# CYAN_EVSE_Logic_board_v1_2.net
KiCad netlist of a schematic drawn in Altium Designer
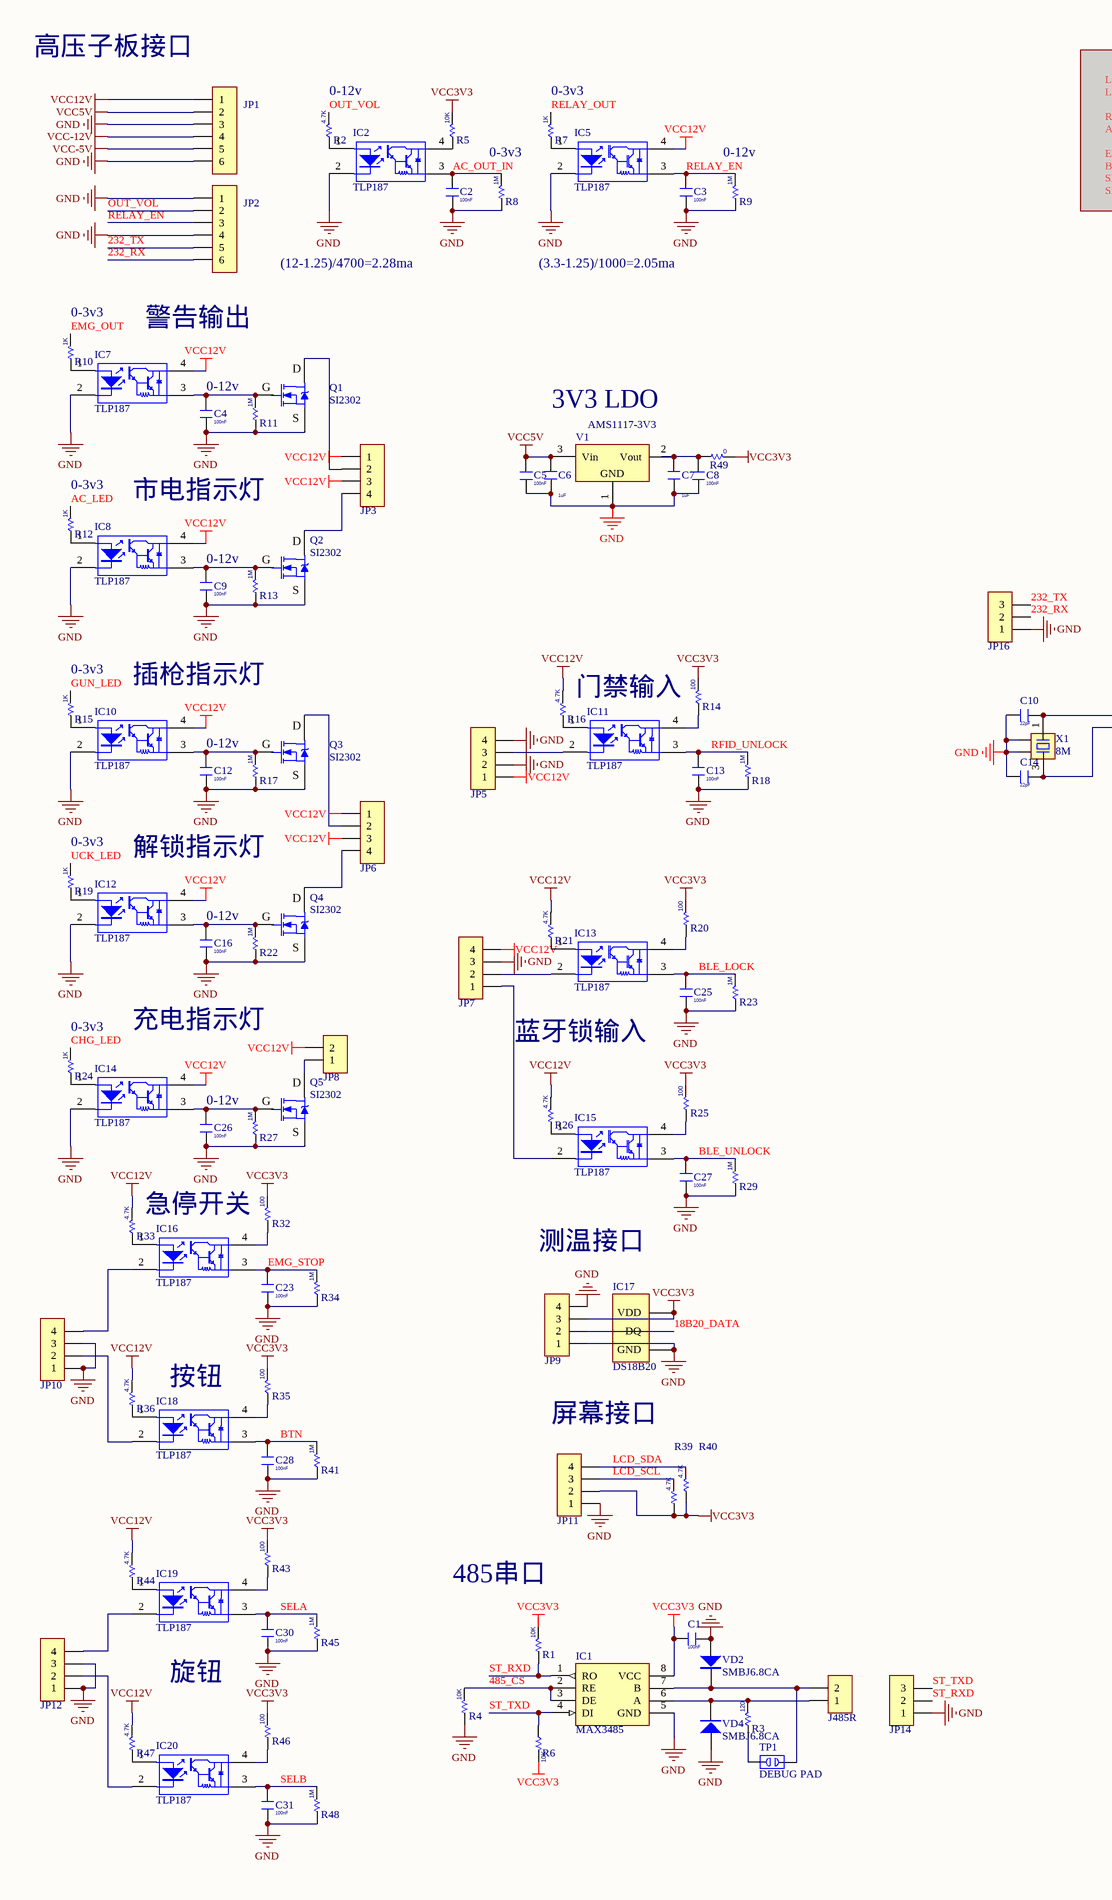
[diagram p0: CYAN_EVSE_Logic_board_v1.2.SchDoc, left]
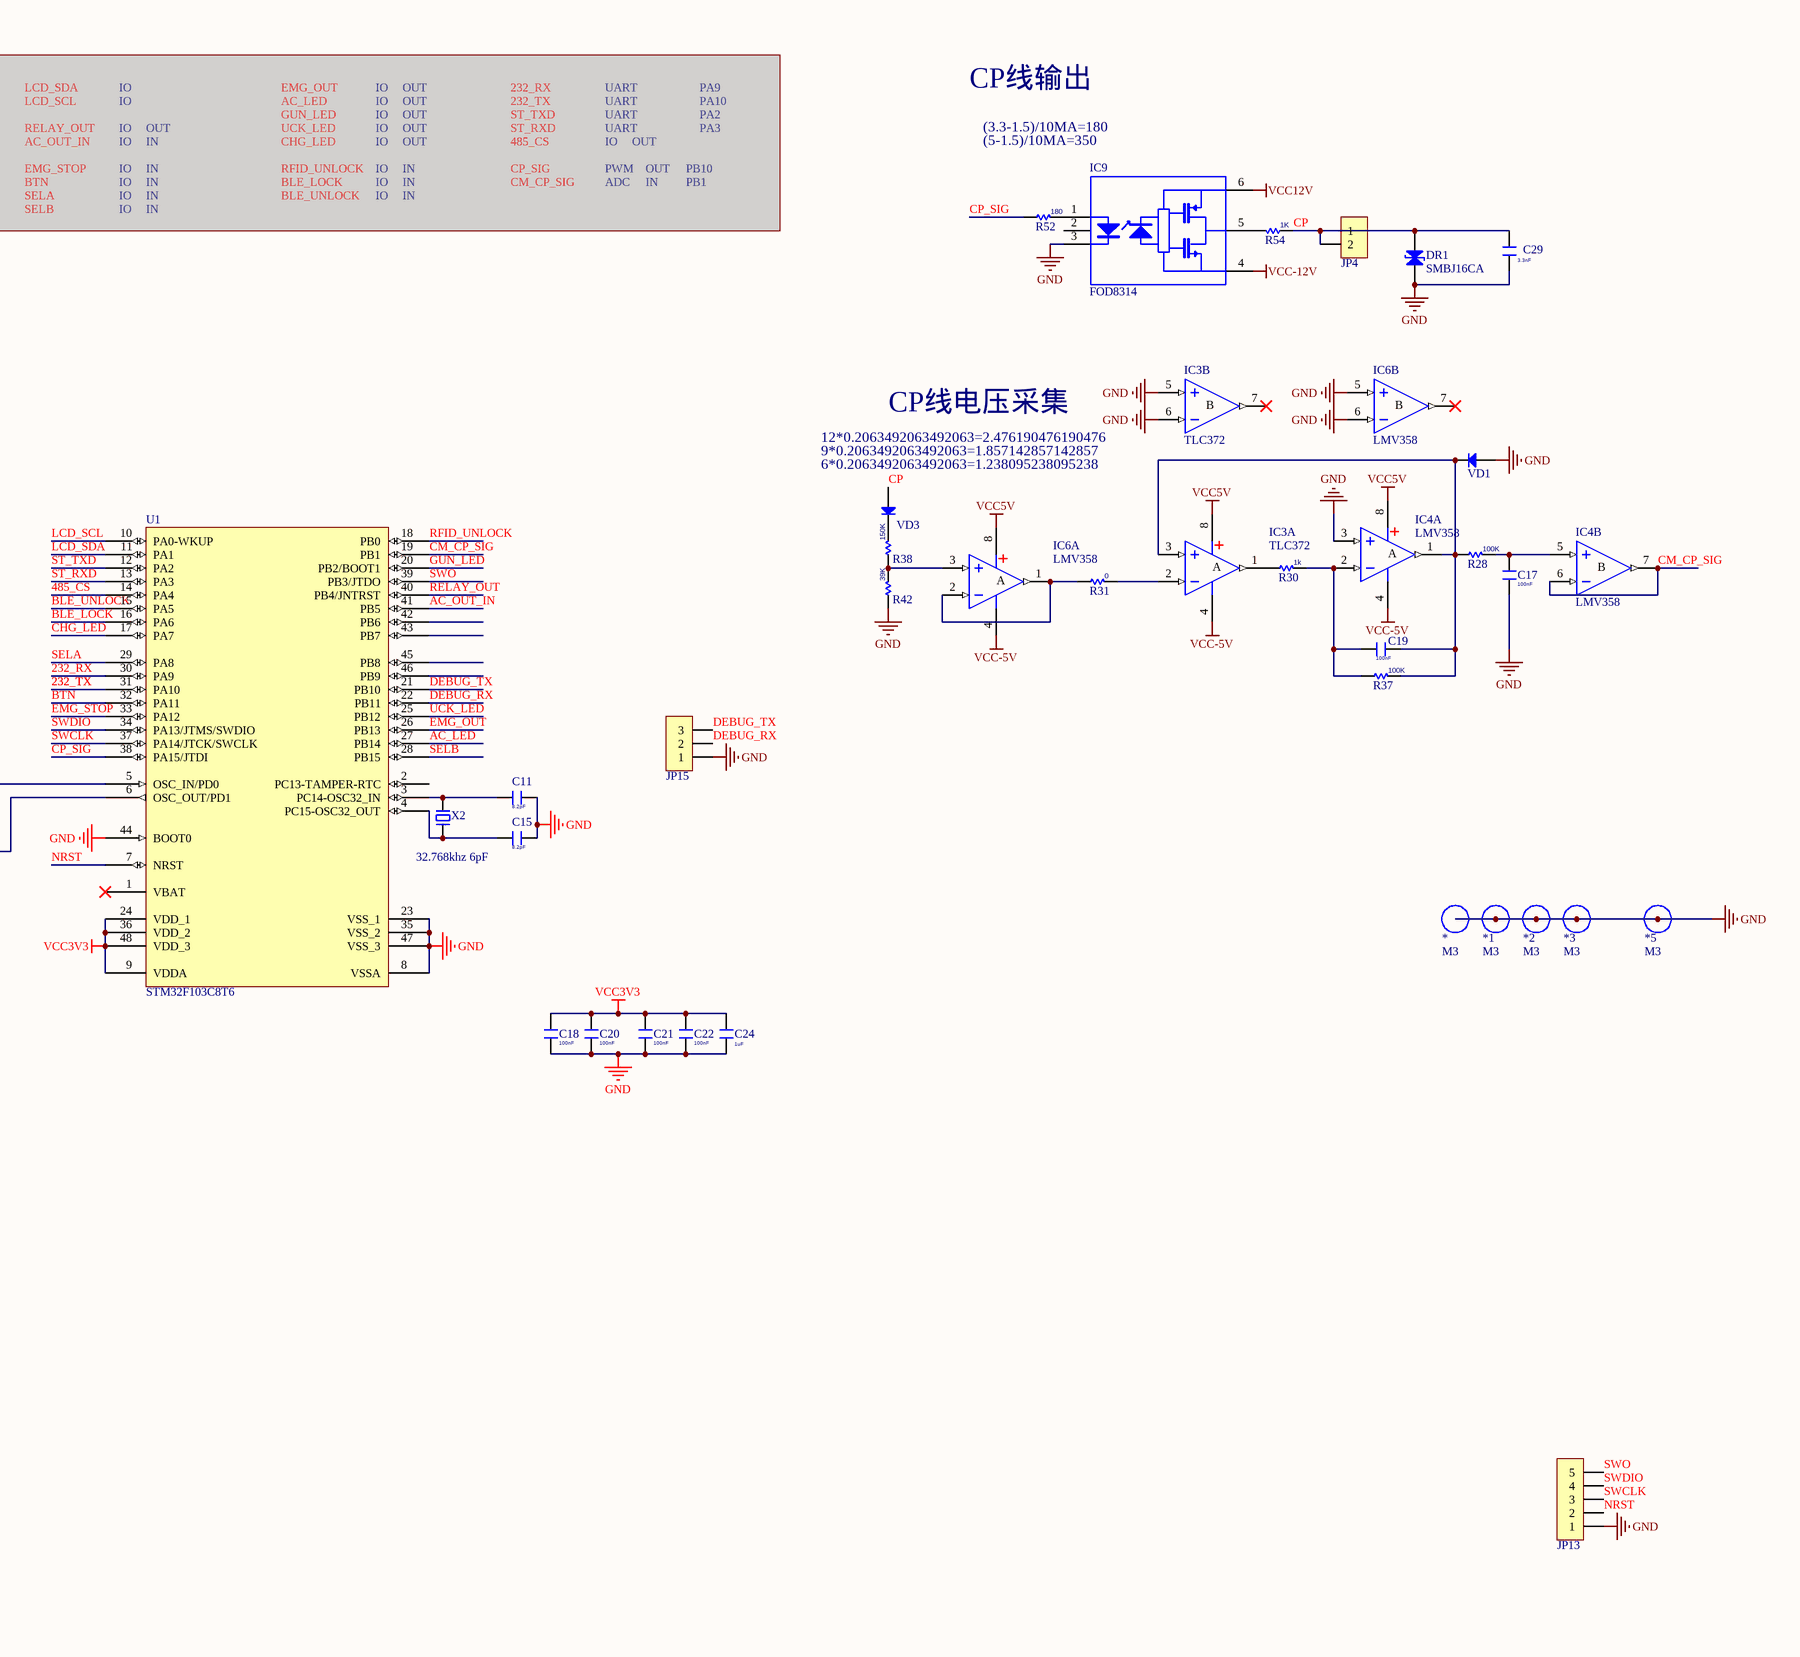
[diagram p1: CYAN_EVSE_Logic_board_v1.2.SchDoc, right]

(export (version "E")
  (design (tool "Eeschema 10.0.6"))
  (components
    (comp (ref "*")
      (value "M3")
      (footprint "M3 125X300")
      (description "铜柱孔")
      (libsource (lib "未分类器件") (part "M3"))
    )
    (comp (ref "*1")
      (value "M3")
      (footprint "M3 125X300")
      (description "铜柱孔")
      (libsource (lib "未分类器件") (part "M3"))
    )
    (comp (ref "*2")
      (value "M3")
      (footprint "M3 125X300")
      (description "铜柱孔")
      (libsource (lib "未分类器件") (part "M3"))
    )
    (comp (ref "*3")
      (value "M3")
      (footprint "M3 125X300")
      (description "铜柱孔")
      (libsource (lib "未分类器件") (part "M3"))
    )
    (comp (ref "*5")
      (value "M3")
      (footprint "M3 125X300")
      (description "铜柱孔")
      (libsource (lib "未分类器件") (part "M3"))
    )
    (comp (ref "C1")
      (value "100nF")
      (footprint "C 0805")
      (description "无极性贴片电容")
      (fields (field (name "VOLTAGE") "20V") (field (name "Comment") "C"))
      (libsource (lib "电阻-电容-电感") (part "C"))
    )
    (comp (ref "C2")
      (value "100nF")
      (footprint "C 0805")
      (description "无极性贴片电容")
      (fields (field (name "VOLTAGE") "20V") (field (name "Comment") "C"))
      (libsource (lib "电阻-电容-电感") (part "C"))
    )
    (comp (ref "C3")
      (value "100nF")
      (footprint "C 0805")
      (description "无极性贴片电容")
      (fields (field (name "VOLTAGE") "20V") (field (name "Comment") "C"))
      (libsource (lib "电阻-电容-电感") (part "C"))
    )
    (comp (ref "C4")
      (value "100nF")
      (footprint "C 0805")
      (description "无极性贴片电容")
      (fields (field (name "VOLTAGE") "20V") (field (name "Comment") "C"))
      (libsource (lib "电阻-电容-电感") (part "C"))
    )
    (comp (ref "C5")
      (value "100nF")
      (footprint "C 0805")
      (description "无极性贴片电容")
      (fields (field (name "VOLTAGE") "20V") (field (name "Comment") "C"))
      (libsource (lib "电阻-电容-电感") (part "C"))
    )
    (comp (ref "C6")
      (value "1uF")
      (footprint "C 0805")
      (description "无极性贴片电容")
      (fields (field (name "Comment") "C"))
      (libsource (lib "电阻-电容-电感") (part "C"))
    )
    (comp (ref "C7")
      (value "1uF")
      (footprint "C 0805")
      (description "无极性贴片电容")
      (fields (field (name "Comment") "C"))
      (libsource (lib "电阻-电容-电感") (part "C"))
    )
    (comp (ref "C8")
      (value "100nF")
      (footprint "C 0805")
      (description "无极性贴片电容")
      (fields (field (name "VOLTAGE") "20V") (field (name "Comment") "C"))
      (libsource (lib "电阻-电容-电感") (part "C"))
    )
    (comp (ref "C9")
      (value "100nF")
      (footprint "C 0805")
      (description "无极性贴片电容")
      (fields (field (name "VOLTAGE") "20V") (field (name "Comment") "C"))
      (libsource (lib "电阻-电容-电感") (part "C"))
    )
    (comp (ref "C10")
      (value "22pF")
      (footprint "C 0805")
      (description "无极性贴片电容")
      (fields (field (name "VOLTAGE") "20V") (field (name "Comment") "C"))
      (libsource (lib "电阻-电容-电感") (part "C"))
    )
    (comp (ref "C11")
      (value "8.2pF")
      (footprint "C 0805")
      (description "无极性贴片电容")
      (fields (field (name "VOLTAGE") "20V") (field (name "Comment") "C"))
      (libsource (lib "电阻-电容-电感") (part "C"))
    )
    (comp (ref "C12")
      (value "100nF")
      (footprint "C 0805")
      (description "无极性贴片电容")
      (fields (field (name "VOLTAGE") "20V") (field (name "Comment") "C"))
      (libsource (lib "电阻-电容-电感") (part "C"))
    )
    (comp (ref "C13")
      (value "100nF")
      (footprint "C 0805")
      (description "无极性贴片电容")
      (fields (field (name "VOLTAGE") "20V") (field (name "Comment") "C"))
      (libsource (lib "电阻-电容-电感") (part "C"))
    )
    (comp (ref "C14")
      (value "22pF")
      (footprint "C 0805")
      (description "无极性贴片电容")
      (fields (field (name "VOLTAGE") "20V") (field (name "Comment") "C"))
      (libsource (lib "电阻-电容-电感") (part "C"))
    )
    (comp (ref "C15")
      (value "8.2pF")
      (footprint "C 0805")
      (description "无极性贴片电容")
      (fields (field (name "VOLTAGE") "20V") (field (name "Comment") "C"))
      (libsource (lib "电阻-电容-电感") (part "C"))
    )
    (comp (ref "C16")
      (value "100nF")
      (footprint "C 0805")
      (description "无极性贴片电容")
      (fields (field (name "VOLTAGE") "20V") (field (name "Comment") "C"))
      (libsource (lib "电阻-电容-电感") (part "C"))
    )
    (comp (ref "C17")
      (value "100nF")
      (footprint "C 0805")
      (description "无极性贴片电容")
      (fields (field (name "VOLTAGE") "20V") (field (name "Comment") "C"))
      (libsource (lib "电阻-电容-电感") (part "C"))
    )
    (comp (ref "C18")
      (value "100nF")
      (footprint "C 0805")
      (description "无极性贴片电容")
      (fields (field (name "VOLTAGE") "20V") (field (name "Comment") "C"))
      (libsource (lib "电阻-电容-电感") (part "C"))
    )
    (comp (ref "C19")
      (value "100nF")
      (footprint "C 0805")
      (description "无极性贴片电容")
      (fields (field (name "VOLTAGE") "20V") (field (name "Comment") "C"))
      (libsource (lib "电阻-电容-电感") (part "C"))
    )
    (comp (ref "C20")
      (value "100nF")
      (footprint "C 0805")
      (description "无极性贴片电容")
      (fields (field (name "VOLTAGE") "20V") (field (name "Comment") "C"))
      (libsource (lib "电阻-电容-电感") (part "C"))
    )
    (comp (ref "C21")
      (value "100nF")
      (footprint "C 0805")
      (description "无极性贴片电容")
      (fields (field (name "VOLTAGE") "20V") (field (name "Comment") "C"))
      (libsource (lib "电阻-电容-电感") (part "C"))
    )
    (comp (ref "C22")
      (value "100nF")
      (footprint "C 0805")
      (description "无极性贴片电容")
      (fields (field (name "VOLTAGE") "20V") (field (name "Comment") "C"))
      (libsource (lib "电阻-电容-电感") (part "C"))
    )
    (comp (ref "C23")
      (value "100nF")
      (footprint "C 0805")
      (description "无极性贴片电容")
      (fields (field (name "VOLTAGE") "20V") (field (name "Comment") "C"))
      (libsource (lib "电阻-电容-电感") (part "C"))
    )
    (comp (ref "C24")
      (value "1uF")
      (footprint "C 0805")
      (description "无极性贴片电容")
      (fields (field (name "Comment") "C"))
      (libsource (lib "电阻-电容-电感") (part "C"))
    )
    (comp (ref "C25")
      (value "100nF")
      (footprint "C 0805")
      (description "无极性贴片电容")
      (fields (field (name "VOLTAGE") "20V") (field (name "Comment") "C"))
      (libsource (lib "电阻-电容-电感") (part "C"))
    )
    (comp (ref "C26")
      (value "100nF")
      (footprint "C 0805")
      (description "无极性贴片电容")
      (fields (field (name "VOLTAGE") "20V") (field (name "Comment") "C"))
      (libsource (lib "电阻-电容-电感") (part "C"))
    )
    (comp (ref "C27")
      (value "100nF")
      (footprint "C 0805")
      (description "无极性贴片电容")
      (fields (field (name "VOLTAGE") "20V") (field (name "Comment") "C"))
      (libsource (lib "电阻-电容-电感") (part "C"))
    )
    (comp (ref "C28")
      (value "100nF")
      (footprint "C 0805")
      (description "无极性贴片电容")
      (fields (field (name "VOLTAGE") "20V") (field (name "Comment") "C"))
      (libsource (lib "电阻-电容-电感") (part "C"))
    )
    (comp (ref "C29")
      (value "3.3nF")
      (footprint "C 1206")
      (description "无极性贴片电容")
      (fields (field (name "VOLTAGE") "50V") (field (name "Comment") "C"))
      (libsource (lib "电阻-电容-电感") (part "C"))
    )
    (comp (ref "C30")
      (value "100nF")
      (footprint "C 0805")
      (description "无极性贴片电容")
      (fields (field (name "VOLTAGE") "20V") (field (name "Comment") "C"))
      (libsource (lib "电阻-电容-电感") (part "C"))
    )
    (comp (ref "C31")
      (value "100nF")
      (footprint "C 0805")
      (description "无极性贴片电容")
      (fields (field (name "VOLTAGE") "20V") (field (name "Comment") "C"))
      (libsource (lib "电阻-电容-电感") (part "C"))
    )
    (comp (ref "DR1")
      (value "SMBJ16CA")
      (footprint "SMB")
      (description "瞬态电压抑制二极管")
      (libsource (lib "二极管-整流桥") (part "DR"))
    )
    (comp (ref "IC1")
      (value "MAX3485")
      (footprint "SOP8_N")
      (description "RS485总线收发芯片")
      (libsource (lib "IC芯片") (part "MAX487"))
    )
    (comp (ref "IC2")
      (value "TLP187")
      (footprint "SOP6_4.6MM_W1.27_4PIN_N")
      (description "达林顿输出光耦")
      (libsource (lib "传感元件") (part "TLP187"))
    )
    (comp (ref "IC3")
      (value "TLC372")
      (footprint "SOP8_N")
      (description "双路电压比较,MOS下臂输出")
      (libsource (lib "IC芯片") (part "TLC372"))
    )
    (comp (ref "IC4")
      (value "LMV358")
      (footprint "SOP8_N")
      (description "双路运放")
      (libsource (lib "IC芯片") (part "LM358"))
    )
    (comp (ref "IC5")
      (value "TLP187")
      (footprint "SOP6_4.6MM_W1.27_4PIN_N")
      (description "达林顿输出光耦")
      (libsource (lib "传感元件") (part "TLP187"))
    )
    (comp (ref "IC6")
      (value "LMV358")
      (footprint "SOP8_N")
      (description "双路运放")
      (libsource (lib "IC芯片") (part "LM358"))
    )
    (comp (ref "IC7")
      (value "TLP187")
      (footprint "SOP6_4.6MM_W1.27_4PIN_N")
      (description "达林顿输出光耦")
      (libsource (lib "传感元件") (part "TLP187"))
    )
    (comp (ref "IC8")
      (value "TLP187")
      (footprint "SOP6_4.6MM_W1.27_4PIN_N")
      (description "达林顿输出光耦")
      (libsource (lib "传感元件") (part "TLP187"))
    )
    (comp (ref "IC9")
      (value "FOD8314")
      (footprint "SOP6_7MM_WIDE_LEAD_N")
      (description "MOSFET/IGBT 驱动光耦，15-30v 1a")
      (libsource (lib "传感元件") (part "FOD8314"))
    )
    (comp (ref "IC10")
      (value "TLP187")
      (footprint "SOP6_4.6MM_W1.27_4PIN_N")
      (description "达林顿输出光耦")
      (libsource (lib "传感元件") (part "TLP187"))
    )
    (comp (ref "IC11")
      (value "TLP187")
      (footprint "SOP6_4.6MM_W1.27_4PIN_N")
      (description "达林顿输出光耦")
      (libsource (lib "传感元件") (part "TLP187"))
    )
    (comp (ref "IC12")
      (value "TLP187")
      (footprint "SOP6_4.6MM_W1.27_4PIN_N")
      (description "达林顿输出光耦")
      (libsource (lib "传感元件") (part "TLP187"))
    )
    (comp (ref "IC13")
      (value "TLP187")
      (footprint "SOP6_4.6MM_W1.27_4PIN_N")
      (description "达林顿输出光耦")
      (libsource (lib "传感元件") (part "TLP187"))
    )
    (comp (ref "IC14")
      (value "TLP187")
      (footprint "SOP6_4.6MM_W1.27_4PIN_N")
      (description "达林顿输出光耦")
      (libsource (lib "传感元件") (part "TLP187"))
    )
    (comp (ref "IC15")
      (value "TLP187")
      (footprint "SOP6_4.6MM_W1.27_4PIN_N")
      (description "达林顿输出光耦")
      (libsource (lib "传感元件") (part "TLP187"))
    )
    (comp (ref "IC16")
      (value "TLP187")
      (footprint "SOP6_4.6MM_W1.27_4PIN_N")
      (description "达林顿输出光耦")
      (libsource (lib "传感元件") (part "TLP187"))
    )
    (comp (ref "IC17")
      (value "DS18B20")
      (footprint "TO92A")
      (description "数字温度计")
      (libsource (lib "IC芯片") (part "DS18B20"))
    )
    (comp (ref "IC18")
      (value "TLP187")
      (footprint "SOP6_4.6MM_W1.27_4PIN_N")
      (description "达林顿输出光耦")
      (libsource (lib "传感元件") (part "TLP187"))
    )
    (comp (ref "IC19")
      (value "TLP187")
      (footprint "SOP6_4.6MM_W1.27_4PIN_N")
      (description "达林顿输出光耦")
      (libsource (lib "传感元件") (part "TLP187"))
    )
    (comp (ref "IC20")
      (value "TLP187")
      (footprint "SOP6_4.6MM_W1.27_4PIN_N")
      (description "达林顿输出光耦")
      (libsource (lib "传感元件") (part "TLP187"))
    )
    (comp (ref "J485R")
      (value "HDR-1X2")
      (footprint "MC 1,5/ 2-G-3,81")
      (description "2P接插件")
      (libsource (lib "接插件") (part "Header 2"))
    )
    (comp (ref "JP1")
      (value "HDR-1X6")
      (footprint "XH2.54-6P")
      (description "6P接插件")
      (libsource (lib "接插件") (part "Header 6"))
    )
    (comp (ref "JP2")
      (value "HDR-1X6")
      (footprint "XH2.54-6P")
      (description "6P接插件")
      (libsource (lib "接插件") (part "Header 6"))
    )
    (comp (ref "JP3")
      (value "HDR-1X4")
      (footprint "MC 1,5/ 4-G-3,81")
      (description "4P接插件")
      (libsource (lib "") (part "Header 4_1"))
    )
    (comp (ref "JP4")
      (value "HDR-1X2")
      (footprint "MC 1,5/ 2-G-3,81")
      (description "2P接插件")
      (libsource (lib "") (part "Header 2_1"))
    )
    (comp (ref "JP5")
      (value "HDR-1X4")
      (footprint "MC 1,5/ 4-G-3,81")
      (description "4P接插件")
      (libsource (lib "接插件") (part "Header 4"))
    )
    (comp (ref "JP6")
      (value "HDR-1X4")
      (footprint "MC 1,5/ 4-G-3,81")
      (description "4P接插件")
      (libsource (lib "") (part "Header 4_1"))
    )
    (comp (ref "JP7")
      (value "HDR-1X4")
      (footprint "MC 1,5/ 4-G-3,81")
      (description "4P接插件")
      (libsource (lib "接插件") (part "Header 4"))
    )
    (comp (ref "JP8")
      (value "HDR-1X2")
      (footprint "MC 1,5/ 2-G-3,81")
      (description "2P接插件")
      (libsource (lib "接插件") (part "Header 2"))
    )
    (comp (ref "JP9")
      (value "HDR-1X4")
      (footprint "MC 1,5/ 4-G-3,81")
      (description "4P接插件")
      (libsource (lib "接插件") (part "Header 4"))
    )
    (comp (ref "JP10")
      (value "HDR-1X4")
      (footprint "MC 1,5/ 4-G-3,81")
      (description "4P接插件")
      (libsource (lib "接插件") (part "Header 4"))
    )
    (comp (ref "JP11")
      (value "HDR-1X4")
      (footprint "XH2.54-4P")
      (description "4P接插件")
      (libsource (lib "接插件") (part "Header 4"))
    )
    (comp (ref "JP12")
      (value "HDR-1X4")
      (footprint "MC 1,5/ 4-G-3,81")
      (description "4P接插件")
      (libsource (lib "接插件") (part "Header 4"))
    )
    (comp (ref "JP13")
      (value "HDR-1X5")
      (footprint "HDR-1X5")
      (description "5P接插件")
      (libsource (lib "接插件") (part "Header 5"))
    )
    (comp (ref "JP14")
      (value "HDR-1X3")
      (footprint "HDR-1X3")
      (description "3P接插件")
      (libsource (lib "接插件") (part "Header 3"))
    )
    (comp (ref "JP15")
      (value "HDR-1X3")
      (footprint "HDR-1X3")
      (description "3P接插件")
      (libsource (lib "接插件") (part "Header 3"))
    )
    (comp (ref "JP16")
      (value "HDR-1X3")
      (footprint "HDR-1X3")
      (description "3P接插件")
      (libsource (lib "接插件") (part "Header 3"))
    )
    (comp (ref "Q1")
      (value "SI2302")
      (footprint "SOT23-3N")
      (description "N沟道场效应管")
      (libsource (lib "场效应管-可控硅") (part "SI2302"))
    )
    (comp (ref "Q2")
      (value "SI2302")
      (footprint "SOT23-3N")
      (description "N沟道场效应管")
      (libsource (lib "场效应管-可控硅") (part "SI2302"))
    )
    (comp (ref "Q3")
      (value "SI2302")
      (footprint "SOT23-3N")
      (description "N沟道场效应管")
      (libsource (lib "场效应管-可控硅") (part "SI2302"))
    )
    (comp (ref "Q4")
      (value "SI2302")
      (footprint "SOT23-3N")
      (description "N沟道场效应管")
      (libsource (lib "场效应管-可控硅") (part "SI2302"))
    )
    (comp (ref "Q5")
      (value "SI2302")
      (footprint "SOT23-3N")
      (description "N沟道场效应管")
      (libsource (lib "场效应管-可控硅") (part "SI2302"))
    )
    (comp (ref "R1")
      (value "10K")
      (footprint "R 0805")
      (description "贴片电阻")
      (fields (field (name "Comment") "R"))
      (libsource (lib "电阻-电容-电感") (part "R"))
    )
    (comp (ref "R2")
      (value "4.7K")
      (footprint "R 0805")
      (description "贴片电阻")
      (fields (field (name "Comment") "R"))
      (libsource (lib "电阻-电容-电感") (part "R"))
    )
    (comp (ref "R3")
      (value "120")
      (footprint "R 1206")
      (description "贴片电阻")
      (fields (field (name "Comment") "R"))
      (libsource (lib "电阻-电容-电感") (part "R"))
    )
    (comp (ref "R4")
      (value "10K")
      (footprint "R 0805")
      (description "贴片电阻")
      (fields (field (name "Comment") "R"))
      (libsource (lib "电阻-电容-电感") (part "R"))
    )
    (comp (ref "R5")
      (value "10K")
      (footprint "R 0805")
      (description "贴片电阻")
      (fields (field (name "Comment") "R"))
      (libsource (lib "电阻-电容-电感") (part "R"))
    )
    (comp (ref "R6")
      (value "10K")
      (footprint "R 0805")
      (description "贴片电阻")
      (fields (field (name "Comment") "R"))
      (libsource (lib "电阻-电容-电感") (part "R"))
    )
    (comp (ref "R7")
      (value "1K")
      (footprint "R 0805")
      (description "贴片电阻")
      (fields (field (name "Comment") "R"))
      (libsource (lib "电阻-电容-电感") (part "R"))
    )
    (comp (ref "R8")
      (value "1M")
      (footprint "R 0805")
      (description "贴片电阻")
      (fields (field (name "Comment") "R"))
      (libsource (lib "电阻-电容-电感") (part "R"))
    )
    (comp (ref "R9")
      (value "1M")
      (footprint "R 0805")
      (description "贴片电阻")
      (fields (field (name "Comment") "R"))
      (libsource (lib "电阻-电容-电感") (part "R"))
    )
    (comp (ref "R10")
      (value "1K")
      (footprint "R 0805")
      (description "贴片电阻")
      (fields (field (name "Comment") "R"))
      (libsource (lib "电阻-电容-电感") (part "R"))
    )
    (comp (ref "R11")
      (value "1M")
      (footprint "R 0805")
      (description "贴片电阻")
      (fields (field (name "Comment") "R"))
      (libsource (lib "电阻-电容-电感") (part "R"))
    )
    (comp (ref "R12")
      (value "1K")
      (footprint "R 0805")
      (description "贴片电阻")
      (fields (field (name "Comment") "R"))
      (libsource (lib "电阻-电容-电感") (part "R"))
    )
    (comp (ref "R13")
      (value "1M")
      (footprint "R 0805")
      (description "贴片电阻")
      (fields (field (name "Comment") "R"))
      (libsource (lib "电阻-电容-电感") (part "R"))
    )
    (comp (ref "R14")
      (value "100")
      (footprint "R 0805")
      (description "贴片电阻")
      (fields (field (name "Comment") "R"))
      (libsource (lib "电阻-电容-电感") (part "R"))
    )
    (comp (ref "R15")
      (value "1K")
      (footprint "R 0805")
      (description "贴片电阻")
      (fields (field (name "Comment") "R"))
      (libsource (lib "电阻-电容-电感") (part "R"))
    )
    (comp (ref "R16")
      (value "4.7K")
      (footprint "R 0805")
      (description "贴片电阻")
      (fields (field (name "Comment") "R"))
      (libsource (lib "电阻-电容-电感") (part "R"))
    )
    (comp (ref "R17")
      (value "1M")
      (footprint "R 0805")
      (description "贴片电阻")
      (fields (field (name "Comment") "R"))
      (libsource (lib "电阻-电容-电感") (part "R"))
    )
    (comp (ref "R18")
      (value "1M")
      (footprint "R 0805")
      (description "贴片电阻")
      (fields (field (name "Comment") "R"))
      (libsource (lib "电阻-电容-电感") (part "R"))
    )
    (comp (ref "R19")
      (value "1K")
      (footprint "R 0805")
      (description "贴片电阻")
      (fields (field (name "Comment") "R"))
      (libsource (lib "电阻-电容-电感") (part "R"))
    )
    (comp (ref "R20")
      (value "100")
      (footprint "R 0805")
      (description "贴片电阻")
      (fields (field (name "Comment") "R"))
      (libsource (lib "电阻-电容-电感") (part "R"))
    )
    (comp (ref "R21")
      (value "4.7K")
      (footprint "R 0805")
      (description "贴片电阻")
      (fields (field (name "Comment") "R"))
      (libsource (lib "电阻-电容-电感") (part "R"))
    )
    (comp (ref "R22")
      (value "1M")
      (footprint "R 0805")
      (description "贴片电阻")
      (fields (field (name "Comment") "R"))
      (libsource (lib "电阻-电容-电感") (part "R"))
    )
    (comp (ref "R23")
      (value "1M")
      (footprint "R 0805")
      (description "贴片电阻")
      (fields (field (name "Comment") "R"))
      (libsource (lib "电阻-电容-电感") (part "R"))
    )
    (comp (ref "R24")
      (value "1K")
      (footprint "R 0805")
      (description "贴片电阻")
      (fields (field (name "Comment") "R"))
      (libsource (lib "电阻-电容-电感") (part "R"))
    )
    (comp (ref "R25")
      (value "100")
      (footprint "R 0805")
      (description "贴片电阻")
      (fields (field (name "Comment") "R"))
      (libsource (lib "电阻-电容-电感") (part "R"))
    )
    (comp (ref "R26")
      (value "4.7K")
      (footprint "R 0805")
      (description "贴片电阻")
      (fields (field (name "Comment") "R"))
      (libsource (lib "电阻-电容-电感") (part "R"))
    )
    (comp (ref "R27")
      (value "1M")
      (footprint "R 0805")
      (description "贴片电阻")
      (fields (field (name "Comment") "R"))
      (libsource (lib "电阻-电容-电感") (part "R"))
    )
    (comp (ref "R28")
      (value "100K")
      (footprint "R 0805")
      (description "贴片电阻")
      (fields (field (name "Comment") "R"))
      (libsource (lib "电阻-电容-电感") (part "R"))
    )
    (comp (ref "R29")
      (value "1M")
      (footprint "R 0805")
      (description "贴片电阻")
      (fields (field (name "Comment") "R"))
      (libsource (lib "电阻-电容-电感") (part "R"))
    )
    (comp (ref "R30")
      (value "1k")
      (footprint "R 0805")
      (description "贴片电阻")
      (fields (field (name "Comment") "R"))
      (libsource (lib "电阻-电容-电感") (part "R"))
    )
    (comp (ref "R31")
      (value "0")
      (footprint "R 0805")
      (description "贴片电阻")
      (fields (field (name "Comment") "R"))
      (libsource (lib "电阻-电容-电感") (part "R"))
    )
    (comp (ref "R32")
      (value "100")
      (footprint "R 0805")
      (description "贴片电阻")
      (fields (field (name "Comment") "R"))
      (libsource (lib "电阻-电容-电感") (part "R"))
    )
    (comp (ref "R33")
      (value "4.7K")
      (footprint "R 0805")
      (description "贴片电阻")
      (fields (field (name "Comment") "R"))
      (libsource (lib "电阻-电容-电感") (part "R"))
    )
    (comp (ref "R34")
      (value "1M")
      (footprint "R 0805")
      (description "贴片电阻")
      (fields (field (name "Comment") "R"))
      (libsource (lib "电阻-电容-电感") (part "R"))
    )
    (comp (ref "R35")
      (value "100")
      (footprint "R 0805")
      (description "贴片电阻")
      (fields (field (name "Comment") "R"))
      (libsource (lib "电阻-电容-电感") (part "R"))
    )
    (comp (ref "R36")
      (value "4.7K")
      (footprint "R 0805")
      (description "贴片电阻")
      (fields (field (name "Comment") "R"))
      (libsource (lib "电阻-电容-电感") (part "R"))
    )
    (comp (ref "R37")
      (value "100K")
      (footprint "R 0805")
      (description "贴片电阻")
      (fields (field (name "Comment") "R"))
      (libsource (lib "电阻-电容-电感") (part "R"))
    )
    (comp (ref "R38")
      (value "150K")
      (footprint "R 0805")
      (description "贴片电阻")
      (fields (field (name "Comment") "R"))
      (libsource (lib "电阻-电容-电感") (part "R"))
    )
    (comp (ref "R39")
      (value "4.7K")
      (footprint "R 0805")
      (description "贴片电阻")
      (fields (field (name "Comment") "R"))
      (libsource (lib "电阻-电容-电感") (part "R"))
    )
    (comp (ref "R40")
      (value "4.7K")
      (footprint "R 0805")
      (description "贴片电阻")
      (fields (field (name "Comment") "R"))
      (libsource (lib "电阻-电容-电感") (part "R"))
    )
    (comp (ref "R41")
      (value "1M")
      (footprint "R 0805")
      (description "贴片电阻")
      (fields (field (name "Comment") "R"))
      (libsource (lib "电阻-电容-电感") (part "R"))
    )
    (comp (ref "R42")
      (value "39K")
      (footprint "R 0805")
      (description "贴片电阻")
      (fields (field (name "Comment") "R"))
      (libsource (lib "电阻-电容-电感") (part "R"))
    )
    (comp (ref "R43")
      (value "100")
      (footprint "R 0805")
      (description "贴片电阻")
      (fields (field (name "Comment") "R"))
      (libsource (lib "电阻-电容-电感") (part "R"))
    )
    (comp (ref "R44")
      (value "4.7K")
      (footprint "R 0805")
      (description "贴片电阻")
      (fields (field (name "Comment") "R"))
      (libsource (lib "电阻-电容-电感") (part "R"))
    )
    (comp (ref "R45")
      (value "1M")
      (footprint "R 0805")
      (description "贴片电阻")
      (fields (field (name "Comment") "R"))
      (libsource (lib "电阻-电容-电感") (part "R"))
    )
    (comp (ref "R46")
      (value "100")
      (footprint "R 0805")
      (description "贴片电阻")
      (fields (field (name "Comment") "R"))
      (libsource (lib "电阻-电容-电感") (part "R"))
    )
    (comp (ref "R47")
      (value "4.7K")
      (footprint "R 0805")
      (description "贴片电阻")
      (fields (field (name "Comment") "R"))
      (libsource (lib "电阻-电容-电感") (part "R"))
    )
    (comp (ref "R48")
      (value "1M")
      (footprint "R 0805")
      (description "贴片电阻")
      (fields (field (name "Comment") "R"))
      (libsource (lib "电阻-电容-电感") (part "R"))
    )
    (comp (ref "R49")
      (value "0")
      (footprint "R 0805")
      (description "贴片电阻")
      (fields (field (name "Comment") "R"))
      (libsource (lib "电阻-电容-电感") (part "R"))
    )
    (comp (ref "R52")
      (value "180")
      (footprint "R 0805")
      (description "贴片电阻")
      (fields (field (name "Comment") "R"))
      (libsource (lib "电阻-电容-电感") (part "R"))
    )
    (comp (ref "R54")
      (value "1K")
      (footprint "R 1206")
      (description "贴片电阻")
      (fields (field (name "Comment") "R"))
      (libsource (lib "电阻-电容-电感") (part "R"))
    )
    (comp (ref "TP1")
      (value "DEBUG PAD")
      (footprint "DEBUG PAD2")
      (description "调试断点焊盘")
      (libsource (lib "未分类器件") (part "DEBUG"))
    )
    (comp (ref "U1")
      (value "STM32F103C8T6")
      (footprint "LQFP48 7X7_M")
      (description "Flaah:64/RAM:20/IO:36")
      (libsource (lib "STM32系列单片机") (part "STM32F103C8T6"))
    )
    (comp (ref "V1")
      (value "AMS1117-3V3")
      (footprint "SOT223_L")
      (description "三端稳压芯片")
      (libsource (lib "IC芯片") (part "AMS1117"))
    )
    (comp (ref "VD1")
      (value "1N4148")
      (footprint "SOD-323")
      (description "高速开关二极管")
      (libsource (lib "二极管-整流桥") (part "1N4148"))
    )
    (comp (ref "VD2")
      (value "SMBJ6.8CA")
      (footprint "SMB")
      (description "肖特基二极管")
      (libsource (lib "二极管-整流桥") (part "SS14"))
    )
    (comp (ref "VD3")
      (value "1N4148")
      (footprint "SOD-323")
      (description "高速开关二极管")
      (libsource (lib "二极管-整流桥") (part "1N4148"))
    )
    (comp (ref "VD4")
      (value "SMBJ6.8CA")
      (footprint "SMB")
      (description "肖特基二极管")
      (libsource (lib "二极管-整流桥") (part "SS14"))
    )
    (comp (ref "X1")
      (value "8M")
      (footprint "XTAL-3225")
      (description "4脚晶振")
      (libsource (lib "保险丝-晶振") (part "XTAL-4"))
    )
    (comp (ref "X2")
      (value "32.768khz 6pF")
      (footprint "XTAL-3215")
      (description "2脚晶振")
      (libsource (lib "保险丝-晶振") (part "XTAL-2"))
    )
  )
  (nets
    (net (code "1") (name "/18B20_DATA") (class "Default")
      (node (ref "IC17") (pin "2") (pinfunction "DQ_2") (pintype "passive"))
      (node (ref "JP9") (pin "2") (pinfunction "2_2") (pintype "passive"))
    )
    (net (code "2") (name "/232_RX") (class "Default")
      (node (ref "JP16") (pin "2") (pinfunction "2_2") (pintype "passive"))
      (node (ref "JP2") (pin "6") (pinfunction "6_6") (pintype "passive"))
      (node (ref "U1") (pin "30") (pinfunction "PA9_30") (pintype "bidirectional"))
    )
    (net (code "3") (name "/232_TX") (class "Default")
      (node (ref "JP16") (pin "3") (pinfunction "3_3") (pintype "passive"))
      (node (ref "JP2") (pin "5") (pinfunction "5_5") (pintype "passive"))
      (node (ref "U1") (pin "31") (pinfunction "PA10_31") (pintype "bidirectional"))
    )
    (net (code "4") (name "/485_CS") (class "Default")
      (node (ref "IC1") (pin "2") (pinfunction "RE_2") (pintype "passive"))
      (node (ref "IC1") (pin "3") (pinfunction "DE_3") (pintype "passive"))
      (node (ref "R4") (pin "2") (pinfunction "2_2") (pintype "passive"))
      (node (ref "U1") (pin "14") (pinfunction "PA4_14") (pintype "bidirectional"))
    )
    (net (code "5") (name "/AC_LED") (class "Default")
      (node (ref "R12") (pin "2") (pinfunction "2_2") (pintype "passive"))
      (node (ref "U1") (pin "27") (pinfunction "PB14_27") (pintype "bidirectional"))
    )
    (net (code "6") (name "/AC_OUT_IN") (class "Default")
      (node (ref "C2") (pin "2") (pinfunction "2_2") (pintype "passive"))
      (node (ref "IC2") (pin "3") (pinfunction "E_3") (pintype "passive"))
      (node (ref "R8") (pin "2") (pinfunction "2_2") (pintype "passive"))
      (node (ref "U1") (pin "41") (pinfunction "PB5_41") (pintype "bidirectional"))
    )
    (net (code "7") (name "/BLE_LOCK") (class "Default")
      (node (ref "C25") (pin "2") (pinfunction "2_2") (pintype "passive"))
      (node (ref "IC13") (pin "3") (pinfunction "E_3") (pintype "passive"))
      (node (ref "R23") (pin "2") (pinfunction "2_2") (pintype "passive"))
      (node (ref "U1") (pin "16") (pinfunction "PA6_16") (pintype "bidirectional"))
    )
    (net (code "8") (name "/BLE_UNLOCK") (class "Default")
      (node (ref "C27") (pin "2") (pinfunction "2_2") (pintype "passive"))
      (node (ref "IC15") (pin "3") (pinfunction "E_3") (pintype "passive"))
      (node (ref "R29") (pin "2") (pinfunction "2_2") (pintype "passive"))
      (node (ref "U1") (pin "15") (pinfunction "PA5_15") (pintype "bidirectional"))
    )
    (net (code "9") (name "/BTN") (class "Default")
      (node (ref "C28") (pin "2") (pinfunction "2_2") (pintype "passive"))
      (node (ref "IC18") (pin "3") (pinfunction "E_3") (pintype "passive"))
      (node (ref "R41") (pin "2") (pinfunction "2_2") (pintype "passive"))
      (node (ref "U1") (pin "32") (pinfunction "PA11_32") (pintype "bidirectional"))
    )
    (net (code "10") (name "/CHG_LED") (class "Default")
      (node (ref "R24") (pin "2") (pinfunction "2_2") (pintype "passive"))
      (node (ref "U1") (pin "17") (pinfunction "PA7_17") (pintype "bidirectional"))
    )
    (net (code "11") (name "/CM_CP_SIG") (class "Default")
      (node (ref "IC4") (pin "6") (pinfunction "IN-_6") (pintype "input"))
      (node (ref "IC4") (pin "7") (pinfunction "OUT_7") (pintype "output"))
      (node (ref "U1") (pin "19") (pinfunction "PB1_19") (pintype "bidirectional"))
    )
    (net (code "12") (name "/CP") (class "Default")
      (node (ref "C29") (pin "2") (pinfunction "2_2") (pintype "passive"))
      (node (ref "DR1") (pin "1") (pinfunction "A_1") (pintype "passive"))
      (node (ref "JP4") (pin "1") (pinfunction "1_1") (pintype "passive"))
      (node (ref "JP4") (pin "2") (pinfunction "2_2") (pintype "passive"))
      (node (ref "R54") (pin "1") (pinfunction "1_1") (pintype "passive"))
      (node (ref "VD3") (pin "1") (pinfunction "A_1") (pintype "passive"))
    )
    (net (code "13") (name "/CP_SIG") (class "Default")
      (node (ref "R52") (pin "1") (pinfunction "1_1") (pintype "passive"))
      (node (ref "U1") (pin "38") (pinfunction "PA15/JTDI_38") (pintype "bidirectional"))
    )
    (net (code "14") (name "/DEBUG_RX") (class "Default")
      (node (ref "JP15") (pin "2") (pinfunction "2_2") (pintype "passive"))
      (node (ref "U1") (pin "22") (pinfunction "PB11_22") (pintype "bidirectional"))
    )
    (net (code "15") (name "/DEBUG_TX") (class "Default")
      (node (ref "JP15") (pin "3") (pinfunction "3_3") (pintype "passive"))
      (node (ref "U1") (pin "21") (pinfunction "PB10_21") (pintype "bidirectional"))
    )
    (net (code "16") (name "/EMG_OUT") (class "Default")
      (node (ref "R10") (pin "2") (pinfunction "2_2") (pintype "passive"))
      (node (ref "U1") (pin "26") (pinfunction "PB13_26") (pintype "bidirectional"))
    )
    (net (code "17") (name "/EMG_STOP") (class "Default")
      (node (ref "C23") (pin "2") (pinfunction "2_2") (pintype "passive"))
      (node (ref "IC16") (pin "3") (pinfunction "E_3") (pintype "passive"))
      (node (ref "R34") (pin "2") (pinfunction "2_2") (pintype "passive"))
      (node (ref "U1") (pin "33") (pinfunction "PA12_33") (pintype "bidirectional"))
    )
    (net (code "18") (name "/GUN_LED") (class "Default")
      (node (ref "R15") (pin "2") (pinfunction "2_2") (pintype "passive"))
      (node (ref "U1") (pin "20") (pinfunction "PB2/BOOT1_20") (pintype "bidirectional"))
    )
    (net (code "19") (name "/LCD_SCL") (class "Default")
      (node (ref "JP11") (pin "3") (pinfunction "3_3") (pintype "passive"))
      (node (ref "R39") (pin "2") (pinfunction "2_2") (pintype "passive"))
      (node (ref "U1") (pin "10") (pinfunction "PA0-WKUP_10") (pintype "bidirectional"))
    )
    (net (code "20") (name "/LCD_SDA") (class "Default")
      (node (ref "JP11") (pin "4") (pinfunction "4_4") (pintype "passive"))
      (node (ref "R40") (pin "2") (pinfunction "2_2") (pintype "passive"))
      (node (ref "U1") (pin "11") (pinfunction "PA1_11") (pintype "bidirectional"))
    )
    (net (code "21") (name "/NRST") (class "Default")
      (node (ref "JP13") (pin "2") (pinfunction "2_2") (pintype "passive"))
      (node (ref "U1") (pin "7") (pinfunction "NRST_7") (pintype "bidirectional"))
    )
    (net (code "22") (name "/OUT_VOL") (class "Default")
      (node (ref "JP2") (pin "2") (pinfunction "2_2") (pintype "passive"))
      (node (ref "R2") (pin "2") (pinfunction "2_2") (pintype "passive"))
    )
    (net (code "23") (name "/RELAY_EN") (class "Default")
      (node (ref "C3") (pin "2") (pinfunction "2_2") (pintype "passive"))
      (node (ref "IC5") (pin "3") (pinfunction "E_3") (pintype "passive"))
      (node (ref "JP2") (pin "3") (pinfunction "3_3") (pintype "passive"))
      (node (ref "R9") (pin "2") (pinfunction "2_2") (pintype "passive"))
    )
    (net (code "24") (name "/RELAY_OUT") (class "Default")
      (node (ref "R7") (pin "2") (pinfunction "2_2") (pintype "passive"))
      (node (ref "U1") (pin "40") (pinfunction "PB4/JNTRST_40") (pintype "bidirectional"))
    )
    (net (code "25") (name "/RFID_UNLOCK") (class "Default")
      (node (ref "C13") (pin "2") (pinfunction "2_2") (pintype "passive"))
      (node (ref "IC11") (pin "3") (pinfunction "E_3") (pintype "passive"))
      (node (ref "R18") (pin "2") (pinfunction "2_2") (pintype "passive"))
      (node (ref "U1") (pin "18") (pinfunction "PB0_18") (pintype "bidirectional"))
    )
    (net (code "26") (name "/SELA") (class "Default")
      (node (ref "C30") (pin "2") (pinfunction "2_2") (pintype "passive"))
      (node (ref "IC19") (pin "3") (pinfunction "E_3") (pintype "passive"))
      (node (ref "R45") (pin "2") (pinfunction "2_2") (pintype "passive"))
      (node (ref "U1") (pin "29") (pinfunction "PA8_29") (pintype "bidirectional"))
    )
    (net (code "27") (name "/SELB") (class "Default")
      (node (ref "C31") (pin "2") (pinfunction "2_2") (pintype "passive"))
      (node (ref "IC20") (pin "3") (pinfunction "E_3") (pintype "passive"))
      (node (ref "R48") (pin "2") (pinfunction "2_2") (pintype "passive"))
      (node (ref "U1") (pin "28") (pinfunction "PB15_28") (pintype "bidirectional"))
    )
    (net (code "28") (name "/ST_RXD") (class "Default")
      (node (ref "IC1") (pin "1") (pinfunction "RO_1") (pintype "output"))
      (node (ref "JP14") (pin "2") (pinfunction "2_2") (pintype "passive"))
      (node (ref "R1") (pin "1") (pinfunction "1_1") (pintype "passive"))
      (node (ref "U1") (pin "13") (pinfunction "PA3_13") (pintype "bidirectional"))
    )
    (net (code "29") (name "/ST_TXD") (class "Default")
      (node (ref "IC1") (pin "4") (pinfunction "DI_4") (pintype "input"))
      (node (ref "JP14") (pin "3") (pinfunction "3_3") (pintype "passive"))
      (node (ref "R6") (pin "1") (pinfunction "1_1") (pintype "passive"))
      (node (ref "U1") (pin "12") (pinfunction "PA2_12") (pintype "bidirectional"))
    )
    (net (code "30") (name "/SWCLK") (class "Default")
      (node (ref "JP13") (pin "3") (pinfunction "3_3") (pintype "passive"))
      (node (ref "U1") (pin "37") (pinfunction "PA14/JTCK/SWCLK_37") (pintype "bidirectional"))
    )
    (net (code "31") (name "/SWDIO") (class "Default")
      (node (ref "JP13") (pin "4") (pinfunction "4_4") (pintype "passive"))
      (node (ref "U1") (pin "34") (pinfunction "PA13/JTMS/SWDIO_34") (pintype "bidirectional"))
    )
    (net (code "32") (name "/SWO") (class "Default")
      (node (ref "JP13") (pin "5") (pinfunction "5_5") (pintype "passive"))
      (node (ref "U1") (pin "39") (pinfunction "PB3/JTDO_39") (pintype "bidirectional"))
    )
    (net (code "33") (name "/UCK_LED") (class "Default")
      (node (ref "R19") (pin "2") (pinfunction "2_2") (pintype "passive"))
      (node (ref "U1") (pin "25") (pinfunction "PB12_25") (pintype "bidirectional"))
    )
    (net (code "34") (name "GND") (class "Default")
      (node (ref "*") (pin "0") (pinfunction "0_0") (pintype "passive"))
      (node (ref "*1") (pin "0") (pinfunction "0_0") (pintype "passive"))
      (node (ref "*2") (pin "0") (pinfunction "0_0") (pintype "passive"))
      (node (ref "*3") (pin "0") (pinfunction "0_0") (pintype "passive"))
      (node (ref "*5") (pin "0") (pinfunction "0_0") (pintype "passive"))
      (node (ref "C1") (pin "1") (pinfunction "1_1") (pintype "passive"))
      (node (ref "C10") (pin "2") (pinfunction "2_2") (pintype "passive"))
      (node (ref "C11") (pin "1") (pinfunction "1_1") (pintype "passive"))
      (node (ref "C12") (pin "1") (pinfunction "1_1") (pintype "passive"))
      (node (ref "C13") (pin "1") (pinfunction "1_1") (pintype "passive"))
      (node (ref "C14") (pin "2") (pinfunction "2_2") (pintype "passive"))
      (node (ref "C15") (pin "1") (pinfunction "1_1") (pintype "passive"))
      (node (ref "C16") (pin "1") (pinfunction "1_1") (pintype "passive"))
      (node (ref "C17") (pin "2") (pinfunction "2_2") (pintype "passive"))
      (node (ref "C18") (pin "1") (pinfunction "1_1") (pintype "passive"))
      (node (ref "C2") (pin "1") (pinfunction "1_1") (pintype "passive"))
      (node (ref "C20") (pin "1") (pinfunction "1_1") (pintype "passive"))
      (node (ref "C21") (pin "1") (pinfunction "1_1") (pintype "passive"))
      (node (ref "C22") (pin "1") (pinfunction "1_1") (pintype "passive"))
      (node (ref "C23") (pin "1") (pinfunction "1_1") (pintype "passive"))
      (node (ref "C24") (pin "2") (pinfunction "2_2") (pintype "passive"))
      (node (ref "C25") (pin "1") (pinfunction "1_1") (pintype "passive"))
      (node (ref "C26") (pin "1") (pinfunction "1_1") (pintype "passive"))
      (node (ref "C27") (pin "1") (pinfunction "1_1") (pintype "passive"))
      (node (ref "C28") (pin "1") (pinfunction "1_1") (pintype "passive"))
      (node (ref "C29") (pin "1") (pinfunction "1_1") (pintype "passive"))
      (node (ref "C3") (pin "1") (pinfunction "1_1") (pintype "passive"))
      (node (ref "C30") (pin "1") (pinfunction "1_1") (pintype "passive"))
      (node (ref "C31") (pin "1") (pinfunction "1_1") (pintype "passive"))
      (node (ref "C4") (pin "1") (pinfunction "1_1") (pintype "passive"))
      (node (ref "C5") (pin "1") (pinfunction "1_1") (pintype "passive"))
      (node (ref "C6") (pin "2") (pinfunction "2_2") (pintype "passive"))
      (node (ref "C7") (pin "2") (pinfunction "2_2") (pintype "passive"))
      (node (ref "C8") (pin "1") (pinfunction "1_1") (pintype "passive"))
      (node (ref "C9") (pin "1") (pinfunction "1_1") (pintype "passive"))
      (node (ref "DR1") (pin "2") (pinfunction "K_2") (pintype "passive"))
      (node (ref "IC1") (pin "5") (pinfunction "GND_5") (pintype "passive"))
      (node (ref "IC10") (pin "2") (pinfunction "K_2") (pintype "passive"))
      (node (ref "IC12") (pin "2") (pinfunction "K_2") (pintype "passive"))
      (node (ref "IC14") (pin "2") (pinfunction "K_2") (pintype "passive"))
      (node (ref "IC17") (pin "1") (pinfunction "GND_1") (pintype "passive"))
      (node (ref "IC2") (pin "2") (pinfunction "K_2") (pintype "passive"))
      (node (ref "IC3") (pin "5") (pinfunction "IN+_5") (pintype "input"))
      (node (ref "IC3") (pin "6") (pinfunction "IN-_6") (pintype "input"))
      (node (ref "IC4") (pin "3") (pinfunction "IN+_3") (pintype "input"))
      (node (ref "IC5") (pin "2") (pinfunction "K_2") (pintype "passive"))
      (node (ref "IC6") (pin "5") (pinfunction "IN+_5") (pintype "input"))
      (node (ref "IC6") (pin "6") (pinfunction "IN-_6") (pintype "input"))
      (node (ref "IC7") (pin "2") (pinfunction "K_2") (pintype "passive"))
      (node (ref "IC8") (pin "2") (pinfunction "K_2") (pintype "passive"))
      (node (ref "IC9") (pin "3") (pinfunction "K_3") (pintype "passive"))
      (node (ref "JP1") (pin "3") (pinfunction "3_3") (pintype "passive"))
      (node (ref "JP1") (pin "6") (pinfunction "6_6") (pintype "passive"))
      (node (ref "JP10") (pin "1") (pinfunction "1_1") (pintype "passive"))
      (node (ref "JP10") (pin "3") (pinfunction "3_3") (pintype "passive"))
      (node (ref "JP11") (pin "1") (pinfunction "1_1") (pintype "passive"))
      (node (ref "JP12") (pin "1") (pinfunction "1_1") (pintype "passive"))
      (node (ref "JP12") (pin "3") (pinfunction "3_3") (pintype "passive"))
      (node (ref "JP13") (pin "1") (pinfunction "1_1") (pintype "passive"))
      (node (ref "JP14") (pin "1") (pinfunction "1_1") (pintype "passive"))
      (node (ref "JP15") (pin "1") (pinfunction "1_1") (pintype "passive"))
      (node (ref "JP16") (pin "1") (pinfunction "1_1") (pintype "passive"))
      (node (ref "JP2") (pin "1") (pinfunction "1_1") (pintype "passive"))
      (node (ref "JP2") (pin "4") (pinfunction "4_4") (pintype "passive"))
      (node (ref "JP5") (pin "2") (pinfunction "2_2") (pintype "passive"))
      (node (ref "JP5") (pin "4") (pinfunction "4_4") (pintype "passive"))
      (node (ref "JP7") (pin "3") (pinfunction "3_3") (pintype "passive"))
      (node (ref "JP9") (pin "1") (pinfunction "1_1") (pintype "passive"))
      (node (ref "JP9") (pin "4") (pinfunction "4_4") (pintype "passive"))
      (node (ref "Q1") (pin "2") (pinfunction "S_2") (pintype "passive"))
      (node (ref "Q2") (pin "2") (pinfunction "S_2") (pintype "passive"))
      (node (ref "Q3") (pin "2") (pinfunction "S_2") (pintype "passive"))
      (node (ref "Q4") (pin "2") (pinfunction "S_2") (pintype "passive"))
      (node (ref "Q5") (pin "2") (pinfunction "S_2") (pintype "passive"))
      (node (ref "R11") (pin "1") (pinfunction "1_1") (pintype "passive"))
      (node (ref "R13") (pin "1") (pinfunction "1_1") (pintype "passive"))
      (node (ref "R17") (pin "1") (pinfunction "1_1") (pintype "passive"))
      (node (ref "R18") (pin "1") (pinfunction "1_1") (pintype "passive"))
      (node (ref "R22") (pin "1") (pinfunction "1_1") (pintype "passive"))
      (node (ref "R23") (pin "1") (pinfunction "1_1") (pintype "passive"))
      (node (ref "R27") (pin "1") (pinfunction "1_1") (pintype "passive"))
      (node (ref "R29") (pin "1") (pinfunction "1_1") (pintype "passive"))
      (node (ref "R34") (pin "1") (pinfunction "1_1") (pintype "passive"))
      (node (ref "R4") (pin "1") (pinfunction "1_1") (pintype "passive"))
      (node (ref "R41") (pin "1") (pinfunction "1_1") (pintype "passive"))
      (node (ref "R42") (pin "1") (pinfunction "1_1") (pintype "passive"))
      (node (ref "R45") (pin "1") (pinfunction "1_1") (pintype "passive"))
      (node (ref "R48") (pin "1") (pinfunction "1_1") (pintype "passive"))
      (node (ref "R8") (pin "1") (pinfunction "1_1") (pintype "passive"))
      (node (ref "R9") (pin "1") (pinfunction "1_1") (pintype "passive"))
      (node (ref "U1") (pin "23") (pinfunction "VSS_1_23") (pintype "power_in"))
      (node (ref "U1") (pin "35") (pinfunction "VSS_2_35") (pintype "power_in"))
      (node (ref "U1") (pin "44") (pinfunction "BOOT0_44") (pintype "input"))
      (node (ref "U1") (pin "47") (pinfunction "VSS_3_47") (pintype "power_in"))
      (node (ref "U1") (pin "8") (pinfunction "VSSA_8") (pintype "power_in"))
      (node (ref "V1") (pin "1") (pinfunction "GND_1") (pintype "passive"))
      (node (ref "VD1") (pin "1") (pinfunction "A_1") (pintype "passive"))
      (node (ref "VD2") (pin "1") (pinfunction "A_1") (pintype "passive"))
      (node (ref "VD4") (pin "1") (pinfunction "A_1") (pintype "passive"))
      (node (ref "X1") (pin "2") (pinfunction "2_2") (pintype "passive"))
      (node (ref "X1") (pin "4") (pinfunction "4_4") (pintype "passive"))
    )
    (net (code "35") (name "Net-(IC1-A)") (class "Default")
      (node (ref "IC1") (pin "6") (pinfunction "A_6") (pintype "passive"))
      (node (ref "J485R") (pin "1") (pinfunction "1_1") (pintype "passive"))
      (node (ref "R3") (pin "2") (pinfunction "2_2") (pintype "passive"))
      (node (ref "VD4") (pin "2") (pinfunction "K_2") (pintype "passive"))
    )
    (net (code "36") (name "Net-(IC1-B)") (class "Default")
      (node (ref "IC1") (pin "7") (pinfunction "B_7") (pintype "passive"))
      (node (ref "J485R") (pin "2") (pinfunction "2_2") (pintype "passive"))
      (node (ref "TP1") (pin "2") (pinfunction "2_2") (pintype "passive"))
      (node (ref "VD2") (pin "2") (pinfunction "K_2") (pintype "passive"))
    )
    (net (code "37") (name "Net-(IC2-A)") (class "Default")
      (node (ref "IC2") (pin "1") (pinfunction "A_1") (pintype "passive"))
      (node (ref "R2") (pin "1") (pinfunction "1_1") (pintype "passive"))
    )
    (net (code "38") (name "Net-(IC2-C)") (class "Default")
      (node (ref "IC2") (pin "4") (pinfunction "C_4") (pintype "passive"))
      (node (ref "R5") (pin "1") (pinfunction "1_1") (pintype "passive"))
    )
    (net (code "39") (name "Net-(IC3A-IN+)") (class "Default")
      (node (ref "C19") (pin "1") (pinfunction "1_1") (pintype "passive"))
      (node (ref "IC3") (pin "3") (pinfunction "IN+_3") (pintype "input"))
      (node (ref "IC4") (pin "1") (pinfunction "OUT_1") (pintype "output"))
      (node (ref "R28") (pin "1") (pinfunction "1_1") (pintype "passive"))
      (node (ref "R37") (pin "2") (pinfunction "2_2") (pintype "passive"))
      (node (ref "VD1") (pin "2") (pinfunction "K_2") (pintype "passive"))
    )
    (net (code "40") (name "Net-(IC3A-IN-)") (class "Default")
      (node (ref "IC3") (pin "2") (pinfunction "IN-_2") (pintype "input"))
      (node (ref "R31") (pin "2") (pinfunction "2_2") (pintype "passive"))
    )
    (net (code "41") (name "Net-(IC3A-OUT)") (class "Default")
      (node (ref "IC3") (pin "1") (pinfunction "OUT_1") (pintype "output"))
      (node (ref "R30") (pin "1") (pinfunction "1_1") (pintype "passive"))
    )
    (net (code "42") (name "Net-(IC4A-IN-)") (class "Default")
      (node (ref "C19") (pin "2") (pinfunction "2_2") (pintype "passive"))
      (node (ref "IC4") (pin "2") (pinfunction "IN-_2") (pintype "input"))
      (node (ref "R30") (pin "2") (pinfunction "2_2") (pintype "passive"))
      (node (ref "R37") (pin "1") (pinfunction "1_1") (pintype "passive"))
    )
    (net (code "43") (name "Net-(IC4B-IN+)") (class "Default")
      (node (ref "C17") (pin "1") (pinfunction "1_1") (pintype "passive"))
      (node (ref "IC4") (pin "5") (pinfunction "IN+_5") (pintype "input"))
      (node (ref "R28") (pin "2") (pinfunction "2_2") (pintype "passive"))
    )
    (net (code "44") (name "Net-(IC5-A)") (class "Default")
      (node (ref "IC5") (pin "1") (pinfunction "A_1") (pintype "passive"))
      (node (ref "R7") (pin "1") (pinfunction "1_1") (pintype "passive"))
    )
    (net (code "45") (name "Net-(IC6A-IN+)") (class "Default")
      (node (ref "IC6") (pin "3") (pinfunction "IN+_3") (pintype "input"))
      (node (ref "R38") (pin "1") (pinfunction "1_1") (pintype "passive"))
      (node (ref "R42") (pin "2") (pinfunction "2_2") (pintype "passive"))
    )
    (net (code "46") (name "Net-(IC6A-IN-)") (class "Default")
      (node (ref "IC6") (pin "1") (pinfunction "OUT_1") (pintype "output"))
      (node (ref "IC6") (pin "2") (pinfunction "IN-_2") (pintype "input"))
      (node (ref "R31") (pin "1") (pinfunction "1_1") (pintype "passive"))
    )
    (net (code "47") (name "Net-(IC7-A)") (class "Default")
      (node (ref "IC7") (pin "1") (pinfunction "A_1") (pintype "passive"))
      (node (ref "R10") (pin "1") (pinfunction "1_1") (pintype "passive"))
    )
    (net (code "48") (name "Net-(IC7-E)") (class "Default")
      (node (ref "C4") (pin "2") (pinfunction "2_2") (pintype "passive"))
      (node (ref "IC7") (pin "3") (pinfunction "E_3") (pintype "passive"))
      (node (ref "Q1") (pin "1") (pinfunction "G_1") (pintype "passive"))
      (node (ref "R11") (pin "2") (pinfunction "2_2") (pintype "passive"))
    )
    (net (code "49") (name "Net-(IC8-A)") (class "Default")
      (node (ref "IC8") (pin "1") (pinfunction "A_1") (pintype "passive"))
      (node (ref "R12") (pin "1") (pinfunction "1_1") (pintype "passive"))
    )
    (net (code "50") (name "Net-(IC8-E)") (class "Default")
      (node (ref "C9") (pin "2") (pinfunction "2_2") (pintype "passive"))
      (node (ref "IC8") (pin "3") (pinfunction "E_3") (pintype "passive"))
      (node (ref "Q2") (pin "1") (pinfunction "G_1") (pintype "passive"))
      (node (ref "R13") (pin "2") (pinfunction "2_2") (pintype "passive"))
    )
    (net (code "51") (name "Net-(IC9-A)") (class "Default")
      (node (ref "IC9") (pin "1") (pinfunction "A_1") (pintype "passive"))
      (node (ref "R52") (pin "2") (pinfunction "2_2") (pintype "passive"))
    )
    (net (code "52") (name "Net-(IC9-OUT)") (class "Default")
      (node (ref "IC9") (pin "5") (pinfunction "OUT_5") (pintype "passive"))
      (node (ref "R54") (pin "2") (pinfunction "2_2") (pintype "passive"))
    )
    (net (code "53") (name "Net-(IC10-A)") (class "Default")
      (node (ref "IC10") (pin "1") (pinfunction "A_1") (pintype "passive"))
      (node (ref "R15") (pin "1") (pinfunction "1_1") (pintype "passive"))
    )
    (net (code "54") (name "Net-(IC10-E)") (class "Default")
      (node (ref "C12") (pin "2") (pinfunction "2_2") (pintype "passive"))
      (node (ref "IC10") (pin "3") (pinfunction "E_3") (pintype "passive"))
      (node (ref "Q3") (pin "1") (pinfunction "G_1") (pintype "passive"))
      (node (ref "R17") (pin "2") (pinfunction "2_2") (pintype "passive"))
    )
    (net (code "55") (name "Net-(IC11-A)") (class "Default")
      (node (ref "IC11") (pin "1") (pinfunction "A_1") (pintype "passive"))
      (node (ref "R16") (pin "1") (pinfunction "1_1") (pintype "passive"))
    )
    (net (code "56") (name "Net-(IC11-C)") (class "Default")
      (node (ref "IC11") (pin "4") (pinfunction "C_4") (pintype "passive"))
      (node (ref "R14") (pin "1") (pinfunction "1_1") (pintype "passive"))
    )
    (net (code "57") (name "Net-(IC11-K)") (class "Default")
      (node (ref "IC11") (pin "2") (pinfunction "K_2") (pintype "passive"))
      (node (ref "JP5") (pin "3") (pinfunction "3_3") (pintype "passive"))
    )
    (net (code "58") (name "Net-(IC12-A)") (class "Default")
      (node (ref "IC12") (pin "1") (pinfunction "A_1") (pintype "passive"))
      (node (ref "R19") (pin "1") (pinfunction "1_1") (pintype "passive"))
    )
    (net (code "59") (name "Net-(IC12-E)") (class "Default")
      (node (ref "C16") (pin "2") (pinfunction "2_2") (pintype "passive"))
      (node (ref "IC12") (pin "3") (pinfunction "E_3") (pintype "passive"))
      (node (ref "Q4") (pin "1") (pinfunction "G_1") (pintype "passive"))
      (node (ref "R22") (pin "2") (pinfunction "2_2") (pintype "passive"))
    )
    (net (code "60") (name "Net-(IC13-A)") (class "Default")
      (node (ref "IC13") (pin "1") (pinfunction "A_1") (pintype "passive"))
      (node (ref "R21") (pin "1") (pinfunction "1_1") (pintype "passive"))
    )
    (net (code "61") (name "Net-(IC13-C)") (class "Default")
      (node (ref "IC13") (pin "4") (pinfunction "C_4") (pintype "passive"))
      (node (ref "R20") (pin "1") (pinfunction "1_1") (pintype "passive"))
    )
    (net (code "62") (name "Net-(IC13-K)") (class "Default")
      (node (ref "IC13") (pin "2") (pinfunction "K_2") (pintype "passive"))
      (node (ref "JP7") (pin "2") (pinfunction "2_2") (pintype "passive"))
    )
    (net (code "63") (name "Net-(IC14-A)") (class "Default")
      (node (ref "IC14") (pin "1") (pinfunction "A_1") (pintype "passive"))
      (node (ref "R24") (pin "1") (pinfunction "1_1") (pintype "passive"))
    )
    (net (code "64") (name "Net-(IC14-E)") (class "Default")
      (node (ref "C26") (pin "2") (pinfunction "2_2") (pintype "passive"))
      (node (ref "IC14") (pin "3") (pinfunction "E_3") (pintype "passive"))
      (node (ref "Q5") (pin "1") (pinfunction "G_1") (pintype "passive"))
      (node (ref "R27") (pin "2") (pinfunction "2_2") (pintype "passive"))
    )
    (net (code "65") (name "Net-(IC15-A)") (class "Default")
      (node (ref "IC15") (pin "1") (pinfunction "A_1") (pintype "passive"))
      (node (ref "R26") (pin "1") (pinfunction "1_1") (pintype "passive"))
    )
    (net (code "66") (name "Net-(IC15-C)") (class "Default")
      (node (ref "IC15") (pin "4") (pinfunction "C_4") (pintype "passive"))
      (node (ref "R25") (pin "1") (pinfunction "1_1") (pintype "passive"))
    )
    (net (code "67") (name "Net-(IC15-K)") (class "Default")
      (node (ref "IC15") (pin "2") (pinfunction "K_2") (pintype "passive"))
      (node (ref "JP7") (pin "1") (pinfunction "1_1") (pintype "passive"))
    )
    (net (code "68") (name "Net-(IC16-A)") (class "Default")
      (node (ref "IC16") (pin "1") (pinfunction "A_1") (pintype "passive"))
      (node (ref "R33") (pin "1") (pinfunction "1_1") (pintype "passive"))
    )
    (net (code "69") (name "Net-(IC16-C)") (class "Default")
      (node (ref "IC16") (pin "4") (pinfunction "C_4") (pintype "passive"))
      (node (ref "R32") (pin "1") (pinfunction "1_1") (pintype "passive"))
    )
    (net (code "70") (name "Net-(IC16-K)") (class "Default")
      (node (ref "IC16") (pin "2") (pinfunction "K_2") (pintype "passive"))
      (node (ref "JP10") (pin "4") (pinfunction "4_4") (pintype "passive"))
    )
    (net (code "71") (name "Net-(IC18-A)") (class "Default")
      (node (ref "IC18") (pin "1") (pinfunction "A_1") (pintype "passive"))
      (node (ref "R36") (pin "1") (pinfunction "1_1") (pintype "passive"))
    )
    (net (code "72") (name "Net-(IC18-C)") (class "Default")
      (node (ref "IC18") (pin "4") (pinfunction "C_4") (pintype "passive"))
      (node (ref "R35") (pin "1") (pinfunction "1_1") (pintype "passive"))
    )
    (net (code "73") (name "Net-(IC18-K)") (class "Default")
      (node (ref "IC18") (pin "2") (pinfunction "K_2") (pintype "passive"))
      (node (ref "JP10") (pin "2") (pinfunction "2_2") (pintype "passive"))
    )
    (net (code "74") (name "Net-(IC19-A)") (class "Default")
      (node (ref "IC19") (pin "1") (pinfunction "A_1") (pintype "passive"))
      (node (ref "R44") (pin "1") (pinfunction "1_1") (pintype "passive"))
    )
    (net (code "75") (name "Net-(IC19-C)") (class "Default")
      (node (ref "IC19") (pin "4") (pinfunction "C_4") (pintype "passive"))
      (node (ref "R43") (pin "1") (pinfunction "1_1") (pintype "passive"))
    )
    (net (code "76") (name "Net-(IC19-K)") (class "Default")
      (node (ref "IC19") (pin "2") (pinfunction "K_2") (pintype "passive"))
      (node (ref "JP12") (pin "4") (pinfunction "4_4") (pintype "passive"))
    )
    (net (code "77") (name "Net-(IC20-A)") (class "Default")
      (node (ref "IC20") (pin "1") (pinfunction "A_1") (pintype "passive"))
      (node (ref "R47") (pin "1") (pinfunction "1_1") (pintype "passive"))
    )
    (net (code "78") (name "Net-(IC20-C)") (class "Default")
      (node (ref "IC20") (pin "4") (pinfunction "C_4") (pintype "passive"))
      (node (ref "R46") (pin "1") (pinfunction "1_1") (pintype "passive"))
    )
    (net (code "79") (name "Net-(IC20-K)") (class "Default")
      (node (ref "IC20") (pin "2") (pinfunction "K_2") (pintype "passive"))
      (node (ref "JP12") (pin "2") (pinfunction "2_2") (pintype "passive"))
    )
    (net (code "80") (name "Net-(Q1-D)") (class "Default")
      (node (ref "JP3") (pin "2") (pinfunction "2_2") (pintype "passive"))
      (node (ref "Q1") (pin "3") (pinfunction "D_3") (pintype "passive"))
    )
    (net (code "81") (name "Net-(Q2-D)") (class "Default")
      (node (ref "JP3") (pin "4") (pinfunction "4_4") (pintype "passive"))
      (node (ref "Q2") (pin "3") (pinfunction "D_3") (pintype "passive"))
    )
    (net (code "82") (name "Net-(Q3-D)") (class "Default")
      (node (ref "JP6") (pin "2") (pinfunction "2_2") (pintype "passive"))
      (node (ref "Q3") (pin "3") (pinfunction "D_3") (pintype "passive"))
    )
    (net (code "83") (name "Net-(Q4-D)") (class "Default")
      (node (ref "JP6") (pin "4") (pinfunction "4_4") (pintype "passive"))
      (node (ref "Q4") (pin "3") (pinfunction "D_3") (pintype "passive"))
    )
    (net (code "84") (name "Net-(Q5-D)") (class "Default")
      (node (ref "JP8") (pin "1") (pinfunction "1_1") (pintype "passive"))
      (node (ref "Q5") (pin "3") (pinfunction "D_3") (pintype "passive"))
    )
    (net (code "85") (name "Net-(R3-Pad1)") (class "Default")
      (node (ref "R3") (pin "1") (pinfunction "1_1") (pintype "passive"))
      (node (ref "TP1") (pin "1") (pinfunction "1_1") (pintype "passive"))
    )
    (net (code "86") (name "Net-(U1-OSC_IN{slash}PD0)") (class "Default")
      (node (ref "C10") (pin "1") (pinfunction "1_1") (pintype "passive"))
      (node (ref "U1") (pin "5") (pinfunction "OSC_IN/PD0_5") (pintype "input"))
      (node (ref "X1") (pin "1") (pinfunction "1_1") (pintype "passive"))
    )
    (net (code "87") (name "Net-(U1-OSC_OUT{slash}PD1)") (class "Default")
      (node (ref "C14") (pin "1") (pinfunction "1_1") (pintype "passive"))
      (node (ref "U1") (pin "6") (pinfunction "OSC_OUT/PD1_6") (pintype "output"))
      (node (ref "X1") (pin "3") (pinfunction "3_3") (pintype "passive"))
    )
    (net (code "88") (name "Net-(U1-PC14-OSC32_IN)") (class "Default")
      (node (ref "C11") (pin "2") (pinfunction "2_2") (pintype "passive"))
      (node (ref "U1") (pin "3") (pinfunction "PC14-OSC32_IN_3") (pintype "bidirectional"))
      (node (ref "X2") (pin "2") (pinfunction "2_2") (pintype "passive"))
    )
    (net (code "89") (name "Net-(U1-PC15-OSC32_OUT)") (class "Default")
      (node (ref "C15") (pin "2") (pinfunction "2_2") (pintype "passive"))
      (node (ref "U1") (pin "4") (pinfunction "PC15-OSC32_OUT_4") (pintype "bidirectional"))
      (node (ref "X2") (pin "1") (pinfunction "1_1") (pintype "passive"))
    )
    (net (code "90") (name "Net-(V1-Vout)") (class "Default")
      (node (ref "C7") (pin "1") (pinfunction "1_1") (pintype "passive"))
      (node (ref "C8") (pin "2") (pinfunction "2_2") (pintype "passive"))
      (node (ref "R49") (pin "1") (pinfunction "1_1") (pintype "passive"))
      (node (ref "V1") (pin "2") (pinfunction "Vout_2") (pintype "passive"))
    )
    (net (code "91") (name "Net-(VD3-K)") (class "Default")
      (node (ref "R38") (pin "2") (pinfunction "2_2") (pintype "passive"))
      (node (ref "VD3") (pin "2") (pinfunction "K_2") (pintype "passive"))
    )
    (net (code "92") (name "VCC-5V") (class "Default")
      (node (ref "IC3") (pin "4") (pinfunction "V-_4") (pintype "power_in"))
      (node (ref "IC4") (pin "4") (pinfunction "V-_4") (pintype "power_in"))
      (node (ref "IC6") (pin "4") (pinfunction "V-_4") (pintype "power_in"))
      (node (ref "JP1") (pin "5") (pinfunction "5_5") (pintype "passive"))
    )
    (net (code "93") (name "VCC-12V") (class "Default")
      (node (ref "IC9") (pin "4") (pinfunction "VSS_4") (pintype "passive"))
      (node (ref "JP1") (pin "4") (pinfunction "4_4") (pintype "passive"))
    )
    (net (code "94") (name "VCC3V3") (class "Default")
      (node (ref "C1") (pin "2") (pinfunction "2_2") (pintype "passive"))
      (node (ref "C18") (pin "2") (pinfunction "2_2") (pintype "passive"))
      (node (ref "C20") (pin "2") (pinfunction "2_2") (pintype "passive"))
      (node (ref "C21") (pin "2") (pinfunction "2_2") (pintype "passive"))
      (node (ref "C22") (pin "2") (pinfunction "2_2") (pintype "passive"))
      (node (ref "C24") (pin "1") (pinfunction "1_1") (pintype "passive"))
      (node (ref "IC1") (pin "8") (pinfunction "VCC_8") (pintype "passive"))
      (node (ref "IC17") (pin "3") (pinfunction "VDD_3") (pintype "passive"))
      (node (ref "JP11") (pin "2") (pinfunction "2_2") (pintype "passive"))
      (node (ref "JP9") (pin "3") (pinfunction "3_3") (pintype "passive"))
      (node (ref "R1") (pin "2") (pinfunction "2_2") (pintype "passive"))
      (node (ref "R14") (pin "2") (pinfunction "2_2") (pintype "passive"))
      (node (ref "R20") (pin "2") (pinfunction "2_2") (pintype "passive"))
      (node (ref "R25") (pin "2") (pinfunction "2_2") (pintype "passive"))
      (node (ref "R32") (pin "2") (pinfunction "2_2") (pintype "passive"))
      (node (ref "R35") (pin "2") (pinfunction "2_2") (pintype "passive"))
      (node (ref "R39") (pin "1") (pinfunction "1_1") (pintype "passive"))
      (node (ref "R40") (pin "1") (pinfunction "1_1") (pintype "passive"))
      (node (ref "R43") (pin "2") (pinfunction "2_2") (pintype "passive"))
      (node (ref "R46") (pin "2") (pinfunction "2_2") (pintype "passive"))
      (node (ref "R49") (pin "2") (pinfunction "2_2") (pintype "passive"))
      (node (ref "R5") (pin "2") (pinfunction "2_2") (pintype "passive"))
      (node (ref "R6") (pin "2") (pinfunction "2_2") (pintype "passive"))
      (node (ref "U1") (pin "24") (pinfunction "VDD_1_24") (pintype "power_in"))
      (node (ref "U1") (pin "36") (pinfunction "VDD_2_36") (pintype "power_in"))
      (node (ref "U1") (pin "48") (pinfunction "VDD_3_48") (pintype "power_in"))
      (node (ref "U1") (pin "9") (pinfunction "VDDA_9") (pintype "power_in"))
    )
    (net (code "95") (name "VCC5V") (class "Default")
      (node (ref "C5") (pin "2") (pinfunction "2_2") (pintype "passive"))
      (node (ref "C6") (pin "1") (pinfunction "1_1") (pintype "passive"))
      (node (ref "IC3") (pin "8") (pinfunction "V+_8") (pintype "power_in"))
      (node (ref "IC4") (pin "8") (pinfunction "V+_8") (pintype "power_in"))
      (node (ref "IC6") (pin "8") (pinfunction "V+_8") (pintype "power_in"))
      (node (ref "JP1") (pin "2") (pinfunction "2_2") (pintype "passive"))
      (node (ref "V1") (pin "3") (pinfunction "Vin_3") (pintype "passive"))
    )
    (net (code "96") (name "VCC12V") (class "Default")
      (node (ref "IC10") (pin "4") (pinfunction "C_4") (pintype "passive"))
      (node (ref "IC12") (pin "4") (pinfunction "C_4") (pintype "passive"))
      (node (ref "IC14") (pin "4") (pinfunction "C_4") (pintype "passive"))
      (node (ref "IC5") (pin "4") (pinfunction "C_4") (pintype "passive"))
      (node (ref "IC7") (pin "4") (pinfunction "C_4") (pintype "passive"))
      (node (ref "IC8") (pin "4") (pinfunction "C_4") (pintype "passive"))
      (node (ref "IC9") (pin "6") (pinfunction "VDD_6") (pintype "passive"))
      (node (ref "JP1") (pin "1") (pinfunction "1_1") (pintype "passive"))
      (node (ref "JP3") (pin "1") (pinfunction "1_1") (pintype "passive"))
      (node (ref "JP3") (pin "3") (pinfunction "3_3") (pintype "passive"))
      (node (ref "JP5") (pin "1") (pinfunction "1_1") (pintype "passive"))
      (node (ref "JP6") (pin "1") (pinfunction "1_1") (pintype "passive"))
      (node (ref "JP6") (pin "3") (pinfunction "3_3") (pintype "passive"))
      (node (ref "JP7") (pin "4") (pinfunction "4_4") (pintype "passive"))
      (node (ref "JP8") (pin "2") (pinfunction "2_2") (pintype "passive"))
      (node (ref "R16") (pin "2") (pinfunction "2_2") (pintype "passive"))
      (node (ref "R21") (pin "2") (pinfunction "2_2") (pintype "passive"))
      (node (ref "R26") (pin "2") (pinfunction "2_2") (pintype "passive"))
      (node (ref "R33") (pin "2") (pinfunction "2_2") (pintype "passive"))
      (node (ref "R36") (pin "2") (pinfunction "2_2") (pintype "passive"))
      (node (ref "R44") (pin "2") (pinfunction "2_2") (pintype "passive"))
      (node (ref "R47") (pin "2") (pinfunction "2_2") (pintype "passive"))
    )
    (net (code "97") (name "unconnected-(IC3B-OUT-Pad7)") (class "Default")
      (node (ref "IC3") (pin "7") (pinfunction "OUT_7") (pintype "output+no_connect"))
    )
    (net (code "98") (name "unconnected-(IC6B-OUT-Pad7)") (class "Default")
      (node (ref "IC6") (pin "7") (pinfunction "OUT_7") (pintype "output+no_connect"))
    )
    (net (code "99") (name "unconnected-(IC9-NC-Pad2)") (class "Default")
      (node (ref "IC9") (pin "2") (pinfunction "NC_2") (pintype "passive"))
    )
    (net (code "100") (name "unconnected-(U1-PB6-Pad42)") (class "Default")
      (node (ref "U1") (pin "42") (pinfunction "PB6_42") (pintype "bidirectional"))
    )
    (net (code "101") (name "unconnected-(U1-PB7-Pad43)") (class "Default")
      (node (ref "U1") (pin "43") (pinfunction "PB7_43") (pintype "bidirectional"))
    )
    (net (code "102") (name "unconnected-(U1-PB8-Pad45)") (class "Default")
      (node (ref "U1") (pin "45") (pinfunction "PB8_45") (pintype "bidirectional"))
    )
    (net (code "103") (name "unconnected-(U1-PB9-Pad46)") (class "Default")
      (node (ref "U1") (pin "46") (pinfunction "PB9_46") (pintype "bidirectional"))
    )
    (net (code "104") (name "unconnected-(U1-PC13-TAMPER-RTC-Pad2)") (class "Default")
      (node (ref "U1") (pin "2") (pinfunction "PC13-TAMPER-RTC_2") (pintype "bidirectional"))
    )
    (net (code "105") (name "unconnected-(U1-VBAT-Pad1)") (class "Default")
      (node (ref "U1") (pin "1") (pinfunction "VBAT_1") (pintype "power_in+no_connect"))
    )
  )
)
